# Sensor_Board.net
KiCad netlist of a schematic drawn in Altium Designer
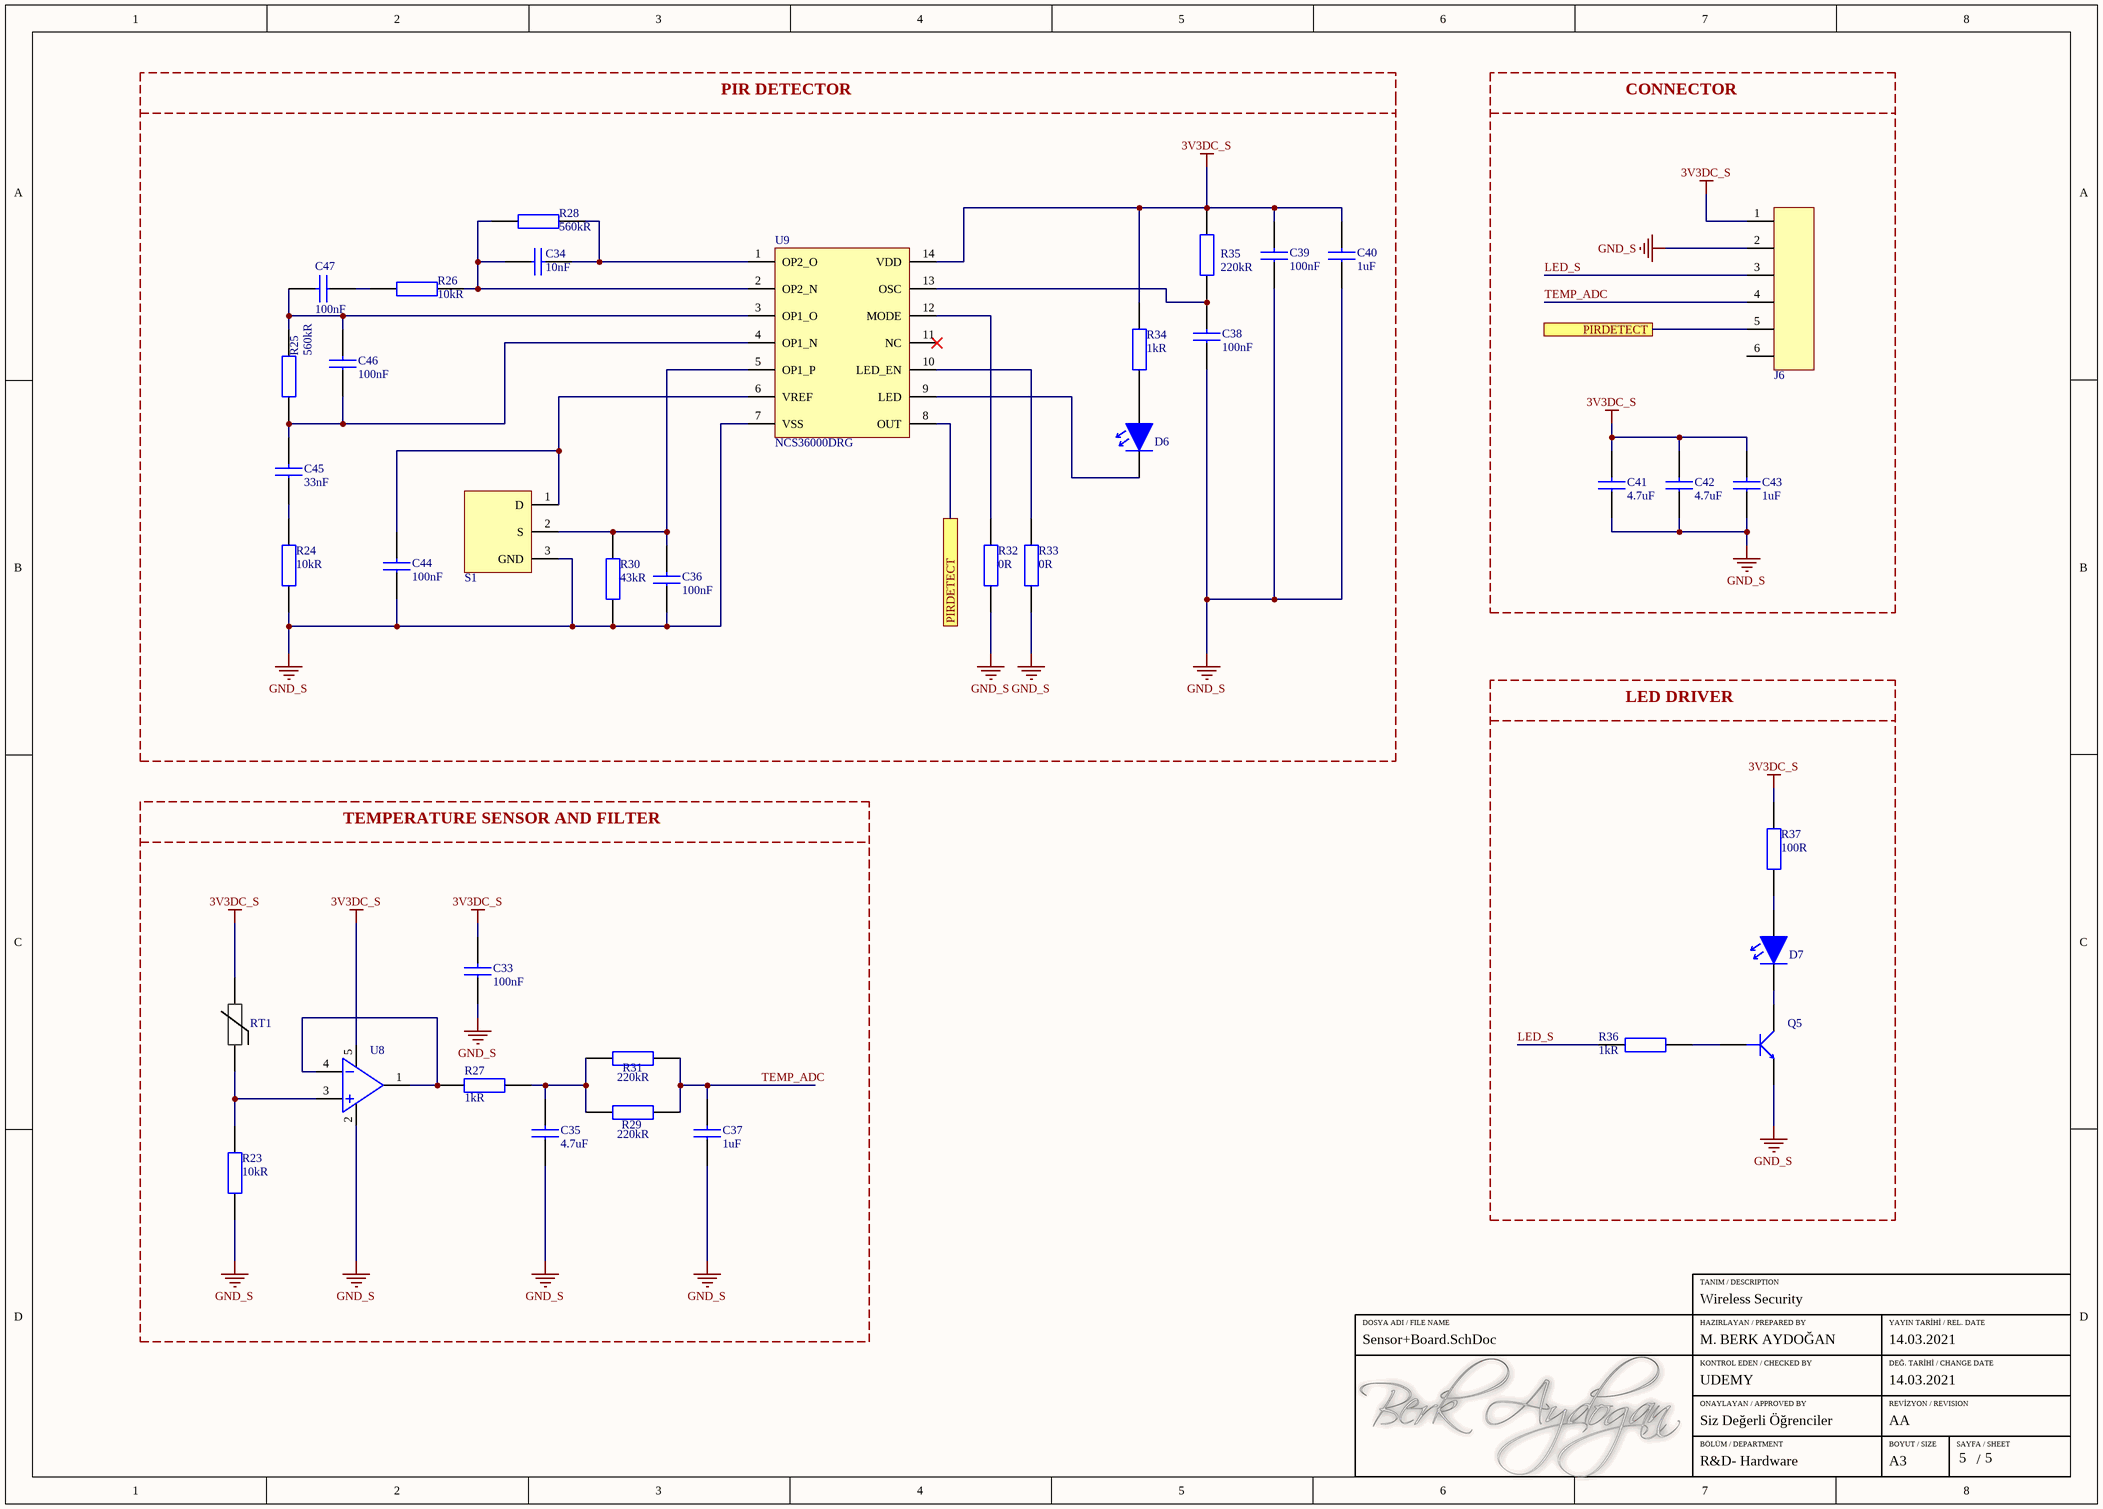
[diagram p0: Sensor+Board.SchDoc]

(export (version "E")
  (design (tool "Eeschema 10.0.6"))
  (components
    (comp (ref "C33")
      (value "C0603C104K5RACTU")
      (footprint "CAP_0603")
      (description "CAP CER 100nF %10 0603 SMD")
      (fields
        (field (name "MANUFACTURER") "KEMET")
        (field (name "TOLERANCE") "10%")
        (field (name "CAPACITANCE") "100nF")
        (field (name "DESIGNED BY") "BERK")
      )
      (libsource (lib "UDEMY_Library") (part "CAP CER 100nF 0603"))
    )
    (comp (ref "C34")
      (value "0603B103K160CT")
      (footprint "CAP_0603")
      (description "CAP CER 10nF %10 0603")
      (fields
        (field (name "MANUFACTURER") "Walsin Technologies")
        (field (name "TOLERANCE") "10%")
        (field (name "CAPACITANCE") "10nF")
        (field (name "DESIGNED BY") "BERK")
      )
      (libsource (lib "UDEMY_Library") (part "CAP CER 10nF 0603"))
    )
    (comp (ref "C35")
      (value "CL21A475KAQNNNE")
      (footprint "CAP_0805")
      (description "CAP CER 4.7uF %10 0805")
      (fields
        (field (name "MANUFACTURER") "Samsung")
        (field (name "TOLERANCE") "10%")
        (field (name "CAPACITANCE") "4.7uF")
        (field (name "DESIGNED BY") "BERK")
      )
      (libsource (lib "UDEMY_Library") (part "CAP CER 4.7uF 0805"))
    )
    (comp (ref "C36")
      (value "C0603C104K5RACTU")
      (footprint "CAP_0603")
      (description "CAP CER 100nF %10 0603 SMD")
      (fields
        (field (name "MANUFACTURER") "KEMET")
        (field (name "TOLERANCE") "10%")
        (field (name "CAPACITANCE") "100nF")
        (field (name "DESIGNED BY") "BERK")
      )
      (libsource (lib "UDEMY_Library") (part "CAP CER 100nF 0603"))
    )
    (comp (ref "C37")
      (value "CL21B105KBFNNNE")
      (footprint "CAP_0805")
      (description "CAP CER 1uF %10 0805")
      (fields
        (field (name "MANUFACTURER") "Samsung")
        (field (name "TOLERANCE") "10%")
        (field (name "CAPACITANCE") "1uF")
        (field (name "DESIGNED BY") "BERK")
      )
      (libsource (lib "UDEMY_Library") (part "CAP CER 1uF 0805"))
    )
    (comp (ref "C38")
      (value "C0603C104K5RACTU")
      (footprint "CAP_0603")
      (description "CAP CER 100nF %10 0603 SMD")
      (fields
        (field (name "MANUFACTURER") "KEMET")
        (field (name "TOLERANCE") "10%")
        (field (name "CAPACITANCE") "100nF")
        (field (name "DESIGNED BY") "BERK")
      )
      (libsource (lib "UDEMY_Library") (part "CAP CER 100nF 0603"))
    )
    (comp (ref "C39")
      (value "C0603C104K5RACTU")
      (footprint "CAP_0603")
      (description "CAP CER 100nF %10 0603 SMD")
      (fields
        (field (name "MANUFACTURER") "KEMET")
        (field (name "TOLERANCE") "10%")
        (field (name "CAPACITANCE") "100nF")
        (field (name "DESIGNED BY") "BERK")
      )
      (libsource (lib "UDEMY_Library") (part "CAP CER 100nF 0603"))
    )
    (comp (ref "C40")
      (value "CL21B105KBFNNNE")
      (footprint "CAP_0805")
      (description "CAP CER 1uF %10 0805")
      (fields
        (field (name "MANUFACTURER") "Samsung")
        (field (name "TOLERANCE") "10%")
        (field (name "CAPACITANCE") "1uF")
        (field (name "DESIGNED BY") "BERK")
      )
      (libsource (lib "UDEMY_Library") (part "CAP CER 1uF 0805"))
    )
    (comp (ref "C41")
      (value "CL21A475KAQNNNE")
      (footprint "CAP_0805")
      (description "CAP CER 4.7uF %10 0805")
      (fields
        (field (name "MANUFACTURER") "Samsung")
        (field (name "TOLERANCE") "10%")
        (field (name "CAPACITANCE") "4.7uF")
        (field (name "DESIGNED BY") "BERK")
      )
      (libsource (lib "UDEMY_Library") (part "CAP CER 4.7uF 0805"))
    )
    (comp (ref "C42")
      (value "CL21A475KAQNNNE")
      (footprint "CAP_0805")
      (description "CAP CER 4.7uF %10 0805")
      (fields
        (field (name "MANUFACTURER") "Samsung")
        (field (name "TOLERANCE") "10%")
        (field (name "CAPACITANCE") "4.7uF")
        (field (name "DESIGNED BY") "BERK")
      )
      (libsource (lib "UDEMY_Library") (part "CAP CER 4.7uF 0805"))
    )
    (comp (ref "C43")
      (value "CL21B105KBFNNNE")
      (footprint "CAP_0805")
      (description "CAP CER 1uF %10 0805")
      (fields
        (field (name "MANUFACTURER") "Samsung")
        (field (name "TOLERANCE") "10%")
        (field (name "CAPACITANCE") "1uF")
        (field (name "DESIGNED BY") "BERK")
      )
      (libsource (lib "UDEMY_Library") (part "CAP CER 1uF 0805"))
    )
    (comp (ref "C44")
      (value "C0603C104K5RACTU")
      (footprint "CAP_0603")
      (description "CAP CER 100nF %10 0603 SMD")
      (fields
        (field (name "MANUFACTURER") "KEMET")
        (field (name "TOLERANCE") "10%")
        (field (name "CAPACITANCE") "100nF")
        (field (name "DESIGNED BY") "BERK")
      )
      (libsource (lib "UDEMY_Library") (part "CAP CER 100nF 0603"))
    )
    (comp (ref "C45")
      (value "C0603C104K5RACTU")
      (footprint "CAP_0603")
      (description "CAP CER 100nF %10 0603 SMD")
      (fields
        (field (name "MANUFACTURER") "KEMET")
        (field (name "TOLERANCE") "10%")
        (field (name "CAPACITANCE") "33nF")
        (field (name "DESIGNED BY") "BERK")
      )
      (libsource (lib "UDEMY_Library") (part "CAP CER 100nF 0603"))
    )
    (comp (ref "C46")
      (value "C0603C104K5RACTU")
      (footprint "CAP_0603")
      (description "CAP CER 100nF %10 0603 SMD")
      (fields
        (field (name "MANUFACTURER") "KEMET")
        (field (name "TOLERANCE") "10%")
        (field (name "CAPACITANCE") "100nF")
        (field (name "DESIGNED BY") "BERK")
      )
      (libsource (lib "UDEMY_Library") (part "CAP CER 100nF 0603"))
    )
    (comp (ref "C47")
      (value "C0603C104K5RACTU")
      (footprint "CAP_0603")
      (description "CAP CER 100nF %10 0603 SMD")
      (fields
        (field (name "MANUFACTURER") "KEMET")
        (field (name "TOLERANCE") "10%")
        (field (name "CAPACITANCE") "100nF")
        (field (name "DESIGNED BY") "BERK")
      )
      (libsource (lib "UDEMY_Library") (part "CAP CER 100nF 0603"))
    )
    (comp (ref "D6")
      (value "LTST-C171GKT")
      (footprint "LED_GREEN_0805")
      (description "Green 0805 130 º Min 5 mcd Typical 12 mcd Water Clear Lens SMT LED")
      (fields (field (name "MANUFACTURER") "Vishay Lite-On") (field (name "DESIGNED BY") "BERK"))
      (libsource (lib "UDEMY_Library") (part "LED GREEN 0805"))
    )
    (comp (ref "D7")
      (value "LH R974-LP-1")
      (footprint "LED_RED_0805")
      (description "LED Uni-Color Hyper Red 660nm 2-Pin Chip 0805(2012Metric) T/R")
      (fields (field (name "MANUFACTURER") "Osram Opto") (field (name "DESIGNED BY") "BERK"))
      (libsource (lib "UDEMY_Library") (part "LED RED 0805"))
    )
    (comp (ref "J6")
      (value "64800611622")
      (footprint "64800611622")
      (description "1.50mm 6PIN Connector")
      (fields (field (name "MANUFACTURER") "Wurth Electronics"))
      (libsource (lib "UDEMY_Library") (part "64800611622_conn_6pin"))
    )
    (comp (ref "Q5")
      (value "MMBT3904-7-F")
      (footprint "SOT-23F")
      (description "Transistor General Purpose BJT NPN 40 Volt 0.2A Automotive 3-Pin SOT-23")
      (fields (field (name "MANUFACTURER") "Diodes Zetex") (field (name "DESIGNED BY") "BERK"))
      (libsource (lib "UDEMY_Library") (part "MMBT3904-7-F"))
    )
    (comp (ref "R23")
      (value "RC0603FR-0710KL")
      (footprint "RES_0603")
      (description "RES 10K %1 OHM 0603 SMD")
      (fields
        (field (name "MANUFACTURER") "Yageo")
        (field (name "TOLERANCE") "1%")
        (field (name "RESISTANCE") "10kR")
        (field (name "DESIGNED BY") "BERK")
      )
      (libsource (lib "UDEMY_Library") (part "RES 10K OHM 0603"))
    )
    (comp (ref "R24")
      (value "RC0603FR-0710KL")
      (footprint "RES_0603")
      (description "RES 10K %1 OHM 0603 SMD")
      (fields
        (field (name "MANUFACTURER") "Yageo")
        (field (name "TOLERANCE") "1%")
        (field (name "RESISTANCE") "10kR")
        (field (name "DESIGNED BY") "BERK")
      )
      (libsource (lib "UDEMY_Library") (part "RES 10K OHM 0603"))
    )
    (comp (ref "R25")
      (value "RC0603JR-07560KL")
      (footprint "RES_0603")
      (description "RES SMD 560K OHM 5% 1/10W 0603")
      (fields
        (field (name "MANUFACTURER") "Yageo")
        (field (name "TOLERANCE") "5%")
        (field (name "RESISTANCE") "560kR")
        (field (name "DESIGNED BY") "BERK")
      )
      (libsource (lib "UDEMY_Library") (part "RES 560K OHM 0603"))
    )
    (comp (ref "R26")
      (value "RC0603FR-0710KL")
      (footprint "RES_0603")
      (description "RES 10K %1 OHM 0603 SMD")
      (fields
        (field (name "MANUFACTURER") "Yageo")
        (field (name "TOLERANCE") "1%")
        (field (name "RESISTANCE") "10kR")
        (field (name "DESIGNED BY") "BERK")
      )
      (libsource (lib "") (part "RES 10K OHM 0603_1"))
    )
    (comp (ref "R27")
      (value "RC0603FR-0710KL")
      (footprint "RES_0603")
      (description "RES 1K %1 OHM 0603 SMD")
      (fields
        (field (name "MANUFACTURER") "Yageo")
        (field (name "MANUFACTURER PART NUMBER") "RC0603JR-071KL")
        (field (name "RESISTANCE") "1kR")
        (field (name "DESIGNED BY") "BERK")
      )
      (libsource (lib "") (part "RES 1K OHM 0603_1"))
    )
    (comp (ref "R28")
      (value "RC0603JR-07560KL")
      (footprint "RES_0603")
      (description "RES SMD 560K OHM 5% 1/10W 0603")
      (fields
        (field (name "MANUFACTURER") "Yageo")
        (field (name "TOLERANCE") "5%")
        (field (name "RESISTANCE") "560kR")
        (field (name "DESIGNED BY") "BERK")
      )
      (libsource (lib "") (part "RES 560K OHM 0603_1"))
    )
    (comp (ref "R29")
      (value "RC0603JR-07220KL")
      (footprint "RES_0603")
      (description "RES 220K %5 OHM 0603 SMD")
      (fields
        (field (name "MANUFACTURER") "Yageo")
        (field (name "TOLERANCE") "5%")
        (field (name "RESISTANCE") "220kR")
      )
      (libsource (lib "UDEMY_Library") (part "RES 220K OHM 0603"))
    )
    (comp (ref "R30")
      (value "RC0603JR-0743KL")
      (footprint "RES_0603")
      (description "RES 43K %5 OHM 0603 SMD")
      (fields
        (field (name "MANUFACTURER") "Yageo")
        (field (name "TOLERANCE") "5%")
        (field (name "RESISTANCE") "43kR")
        (field (name "DESIGNED BY") "BERK")
      )
      (libsource (lib "UDEMY_Library") (part "RES 43K OHM 0603"))
    )
    (comp (ref "R31")
      (value "RC0603JR-07220KL")
      (footprint "RES_0603")
      (description "RES 220K %5 OHM 0603 SMD")
      (fields
        (field (name "MANUFACTURER") "Yageo")
        (field (name "TOLERANCE") "5%")
        (field (name "RESISTANCE") "220kR")
      )
      (libsource (lib "UDEMY_Library") (part "RES 220K OHM 0603"))
    )
    (comp (ref "R32")
      (value "RC0603JR-070RL")
      (footprint "RES_0603")
      (description "RES 0 %1 OHM 0603 SMD")
      (fields
        (field (name "MANUFACTURER") "Yageo")
        (field (name "TOLERANCE") "1%")
        (field (name "RESISTANCE") "0R")
        (field (name "DESIGNED BY") "BERK")
      )
      (libsource (lib "UDEMY_Library") (part "RES 0 OHM 0603"))
    )
    (comp (ref "R33")
      (value "RC0603JR-070RL")
      (footprint "RES_0603")
      (description "RES 0 %1 OHM 0603 SMD")
      (fields
        (field (name "MANUFACTURER") "Yageo")
        (field (name "TOLERANCE") "1%")
        (field (name "RESISTANCE") "0R")
        (field (name "DESIGNED BY") "BERK")
      )
      (libsource (lib "UDEMY_Library") (part "RES 0 OHM 0603"))
    )
    (comp (ref "R34")
      (value "RC0603FR-0710KL")
      (footprint "RES_0603")
      (description "RES 1K %1 OHM 0603 SMD")
      (fields
        (field (name "MANUFACTURER") "Yageo")
        (field (name "MANUFACTURER PART NUMBER") "RC0603JR-071KL")
        (field (name "RESISTANCE") "1kR")
        (field (name "DESIGNED BY") "BERK")
      )
      (libsource (lib "UDEMY_Library") (part "RES 1K OHM 0603"))
    )
    (comp (ref "R35")
      (value "RC0603JR-07220KL")
      (footprint "RES_0603")
      (description "RES 220K %5 OHM 0603 SMD")
      (fields
        (field (name "MANUFACTURER") "Yageo")
        (field (name "TOLERANCE") "5%")
        (field (name "RESISTANCE") "220kR")
      )
      (libsource (lib "") (part "RES 220K OHM 0603_1"))
    )
    (comp (ref "R36")
      (value "RC0603FR-0710KL")
      (footprint "RES_0603")
      (description "RES 1K %1 OHM 0603 SMD")
      (fields
        (field (name "MANUFACTURER") "Yageo")
        (field (name "MANUFACTURER PART NUMBER") "RC0603JR-071KL")
        (field (name "RESISTANCE") "1kR")
        (field (name "DESIGNED BY") "BERK")
      )
      (libsource (lib "") (part "RES 1K OHM 0603_1"))
    )
    (comp (ref "R37")
      (value "RC0603JR-07100RL")
      (footprint "RES_0603")
      (description "RES 100 %5 OHM 0603 SMD")
      (fields
        (field (name "MANUFACTURER") "Yageo")
        (field (name "TOLERANCE") "5%")
        (field (name "RESISTANCE") "100R")
        (field (name "DESIGNED BY") "BERK")
      )
      (libsource (lib "UDEMY_Library") (part "RES 100 OHM 0603"))
    )
    (comp (ref "RT1")
      (value "TFPT1206L1002FM")
      (footprint "RES_1206")
      (description "Thermistor PTC 10K Ohm 1% 1206")
      (fields
        (field (name "MANUFACTURER") "Vishay Dale")
        (field (name "TOLERANCE") "1%")
        (field (name "DESIGNED BY") "BERK")
      )
      (libsource (lib "UDEMY_Library") (part "TFPT1206L1002FM"))
    )
    (comp (ref "S1")
      (value "LHI 878/3902")
      (footprint "LHI 878")
      (description "SENSOR PYRO DETECTOR DUAL MOTION")
      (fields (field (name "DESIGNED BY") "BERK"))
      (libsource (lib "UDEMY_Library") (part "LHI 878/3902"))
    )
    (comp (ref "U8")
      (value "OPA314AIDBVR")
      (footprint "SOT23-5")
      (description "Op Amp OPA314")
      (fields (field (name "MANUFACTURER") "Texas Instruments") (field (name "DESIGNED BY") "BERK"))
      (libsource (lib "UDEMY_Library") (part "OPA314"))
    )
    (comp (ref "U9")
      (value "NCS36000DRG")
      (footprint "SOIC14")
      (description "PIR Controller Low Noise Amplifiers and LDO Regulator 14-Pin SOIC N T/R")
      (fields (field (name "MANUFACTURER") "ON Semiconductor") (field (name "DESIGNED BY") "BERK"))
      (libsource (lib "UDEMY_Library") (part "NCS36000"))
    )
  )
  (nets
    (net (code "1") (name "/LED_S") (class "Default")
      (node (ref "J6") (pin "3") (pintype "power_in"))
      (node (ref "R36") (pin "1") (pinfunction "1_1") (pintype "passive"))
    )
    (net (code "2") (name "/PIRDETECT") (class "Default")
      (node (ref "J6") (pin "5") (pintype "power_in"))
      (node (ref "U9") (pin "8") (pinfunction "OUT_8") (pintype "passive"))
    )
    (net (code "3") (name "/TEMP_ADC") (class "Default")
      (node (ref "C37") (pin "2") (pinfunction "2_2") (pintype "passive"))
      (node (ref "J6") (pin "4") (pintype "power_in"))
      (node (ref "R29") (pin "2") (pinfunction "2_2") (pintype "passive"))
      (node (ref "R31") (pin "2") (pinfunction "2_2") (pintype "passive"))
    )
    (net (code "4") (name "3V3DC_S") (class "Default")
      (node (ref "C33") (pin "2") (pinfunction "2_2") (pintype "passive"))
      (node (ref "C39") (pin "2") (pinfunction "2_2") (pintype "passive"))
      (node (ref "C40") (pin "2") (pinfunction "2_2") (pintype "passive"))
      (node (ref "C41") (pin "2") (pinfunction "2_2") (pintype "passive"))
      (node (ref "C42") (pin "2") (pinfunction "2_2") (pintype "passive"))
      (node (ref "C43") (pin "2") (pinfunction "2_2") (pintype "passive"))
      (node (ref "J6") (pin "1") (pintype "power_in"))
      (node (ref "R34") (pin "2") (pinfunction "2_2") (pintype "passive"))
      (node (ref "R35") (pin "2") (pinfunction "2_2") (pintype "passive"))
      (node (ref "R37") (pin "2") (pinfunction "2_2") (pintype "passive"))
      (node (ref "RT1") (pin "2") (pinfunction "2_2") (pintype "passive"))
      (node (ref "U8") (pin "5") (pinfunction "5_5") (pintype "passive"))
      (node (ref "U9") (pin "14") (pinfunction "VDD_14") (pintype "passive"))
    )
    (net (code "5") (name "GND_S") (class "Default")
      (node (ref "C33") (pin "1") (pinfunction "1_1") (pintype "passive"))
      (node (ref "C35") (pin "1") (pinfunction "1_1") (pintype "passive"))
      (node (ref "C36") (pin "1") (pinfunction "1_1") (pintype "passive"))
      (node (ref "C37") (pin "1") (pinfunction "1_1") (pintype "passive"))
      (node (ref "C38") (pin "1") (pinfunction "1_1") (pintype "passive"))
      (node (ref "C39") (pin "1") (pinfunction "1_1") (pintype "passive"))
      (node (ref "C40") (pin "1") (pinfunction "1_1") (pintype "passive"))
      (node (ref "C41") (pin "1") (pinfunction "1_1") (pintype "passive"))
      (node (ref "C42") (pin "1") (pinfunction "1_1") (pintype "passive"))
      (node (ref "C43") (pin "1") (pinfunction "1_1") (pintype "passive"))
      (node (ref "C44") (pin "1") (pinfunction "1_1") (pintype "passive"))
      (node (ref "J6") (pin "2") (pintype "power_in"))
      (node (ref "Q5") (pin "2") (pinfunction "E_2") (pintype "power_in"))
      (node (ref "R23") (pin "1") (pinfunction "1_1") (pintype "passive"))
      (node (ref "R24") (pin "1") (pinfunction "1_1") (pintype "passive"))
      (node (ref "R30") (pin "1") (pinfunction "1_1") (pintype "passive"))
      (node (ref "R32") (pin "1") (pinfunction "1_1") (pintype "passive"))
      (node (ref "R33") (pin "1") (pinfunction "1_1") (pintype "passive"))
      (node (ref "S1") (pin "3") (pinfunction "GND_3") (pintype "passive"))
      (node (ref "U8") (pin "2") (pinfunction "2_2") (pintype "passive"))
      (node (ref "U9") (pin "7") (pinfunction "VSS_7") (pintype "passive"))
    )
    (net (code "6") (name "Net-(C35-Pad2)") (class "Default")
      (node (ref "C35") (pin "2") (pinfunction "2_2") (pintype "passive"))
      (node (ref "R27") (pin "2") (pinfunction "2_2") (pintype "passive"))
      (node (ref "R29") (pin "1") (pinfunction "1_1") (pintype "passive"))
      (node (ref "R31") (pin "1") (pinfunction "1_1") (pintype "passive"))
    )
    (net (code "7") (name "Net-(C45-Pad1)") (class "Default")
      (node (ref "C45") (pin "1") (pinfunction "1_1") (pintype "passive"))
      (node (ref "R24") (pin "2") (pinfunction "2_2") (pintype "passive"))
    )
    (net (code "8") (name "Net-(C47-Pad1)") (class "Default")
      (node (ref "C47") (pin "1") (pinfunction "1_1") (pintype "passive"))
      (node (ref "R26") (pin "1") (pinfunction "1_1") (pintype "passive"))
    )
    (net (code "9") (name "Net-(D6-Pad2)") (class "Default")
      (node (ref "D6") (pin "2") (pinfunction "2_2") (pintype "power_in"))
      (node (ref "R34") (pin "1") (pinfunction "1_1") (pintype "passive"))
    )
    (net (code "10") (name "Net-(D7-Pad2)") (class "Default")
      (node (ref "D7") (pin "2") (pinfunction "2_2") (pintype "power_in"))
      (node (ref "R37") (pin "1") (pinfunction "1_1") (pintype "passive"))
    )
    (net (code "11") (name "Net-(Q5-B)") (class "Default")
      (node (ref "Q5") (pin "1") (pinfunction "B_1") (pintype "power_in"))
      (node (ref "R36") (pin "2") (pinfunction "2_2") (pintype "passive"))
    )
    (net (code "12") (name "Net-(Q5-C)") (class "Default")
      (node (ref "D7") (pin "1") (pinfunction "1_1") (pintype "power_in"))
      (node (ref "Q5") (pin "3") (pinfunction "C_3") (pintype "power_in"))
    )
    (net (code "13") (name "Net-(R23-Pad2)") (class "Default")
      (node (ref "R23") (pin "2") (pinfunction "2_2") (pintype "passive"))
      (node (ref "RT1") (pin "1") (pinfunction "1_1") (pintype "passive"))
      (node (ref "U8") (pin "3") (pinfunction "3_3") (pintype "passive"))
    )
    (net (code "14") (name "Net-(R27-Pad1)") (class "Default")
      (node (ref "R27") (pin "1") (pinfunction "1_1") (pintype "passive"))
      (node (ref "U8") (pin "1") (pinfunction "1_1") (pintype "passive"))
      (node (ref "U8") (pin "4") (pinfunction "4_4") (pintype "passive"))
    )
    (net (code "15") (name "Net-(S1-D)") (class "Default")
      (node (ref "C44") (pin "2") (pinfunction "2_2") (pintype "passive"))
      (node (ref "S1") (pin "1") (pinfunction "D_1") (pintype "passive"))
      (node (ref "U9") (pin "6") (pinfunction "VREF_6") (pintype "passive"))
    )
    (net (code "16") (name "Net-(S1-S)") (class "Default")
      (node (ref "C36") (pin "2") (pinfunction "2_2") (pintype "passive"))
      (node (ref "R30") (pin "2") (pinfunction "2_2") (pintype "passive"))
      (node (ref "S1") (pin "2") (pinfunction "S_2") (pintype "passive"))
      (node (ref "U9") (pin "5") (pinfunction "OP1_P_5") (pintype "passive"))
    )
    (net (code "17") (name "Net-(U9-LED)") (class "Default")
      (node (ref "D6") (pin "1") (pinfunction "1_1") (pintype "power_in"))
      (node (ref "U9") (pin "9") (pinfunction "LED_9") (pintype "passive"))
    )
    (net (code "18") (name "Net-(U9-LED_EN)") (class "Default")
      (node (ref "R33") (pin "2") (pinfunction "2_2") (pintype "passive"))
      (node (ref "U9") (pin "10") (pinfunction "LED_EN_10") (pintype "passive"))
    )
    (net (code "19") (name "Net-(U9-MODE)") (class "Default")
      (node (ref "R32") (pin "2") (pinfunction "2_2") (pintype "passive"))
      (node (ref "U9") (pin "12") (pinfunction "MODE_12") (pintype "passive"))
    )
    (net (code "20") (name "Net-(U9-OP1_N)") (class "Default")
      (node (ref "C45") (pin "2") (pinfunction "2_2") (pintype "passive"))
      (node (ref "C46") (pin "1") (pinfunction "1_1") (pintype "passive"))
      (node (ref "R25") (pin "1") (pinfunction "1_1") (pintype "passive"))
      (node (ref "U9") (pin "4") (pinfunction "OP1_N_4") (pintype "passive"))
    )
    (net (code "21") (name "Net-(U9-OP1_O)") (class "Default")
      (node (ref "C46") (pin "2") (pinfunction "2_2") (pintype "passive"))
      (node (ref "C47") (pin "2") (pinfunction "2_2") (pintype "passive"))
      (node (ref "R25") (pin "2") (pinfunction "2_2") (pintype "passive"))
      (node (ref "U9") (pin "3") (pinfunction "OP1_O_3") (pintype "passive"))
    )
    (net (code "22") (name "Net-(U9-OP2_N)") (class "Default")
      (node (ref "C34") (pin "1") (pinfunction "1_1") (pintype "passive"))
      (node (ref "R26") (pin "2") (pinfunction "2_2") (pintype "passive"))
      (node (ref "R28") (pin "1") (pinfunction "1_1") (pintype "passive"))
      (node (ref "U9") (pin "2") (pinfunction "OP2_N_2") (pintype "passive"))
    )
    (net (code "23") (name "Net-(U9-OP2_O)") (class "Default")
      (node (ref "C34") (pin "2") (pinfunction "2_2") (pintype "passive"))
      (node (ref "R28") (pin "2") (pinfunction "2_2") (pintype "passive"))
      (node (ref "U9") (pin "1") (pinfunction "OP2_O_1") (pintype "passive"))
    )
    (net (code "24") (name "Net-(U9-OSC)") (class "Default")
      (node (ref "C38") (pin "2") (pinfunction "2_2") (pintype "passive"))
      (node (ref "R35") (pin "1") (pinfunction "1_1") (pintype "passive"))
      (node (ref "U9") (pin "13") (pinfunction "OSC_13") (pintype "passive"))
    )
    (net (code "25") (name "unconnected-(J6-Pad6)") (class "Default")
      (node (ref "J6") (pin "6") (pintype "power_in"))
    )
    (net (code "26") (name "unconnected-(U9-NC-Pad11)") (class "Default")
      (node (ref "U9") (pin "11") (pinfunction "NC_11") (pintype "passive+no_connect"))
    )
  )
)
